# GasSensorCentral_v2_1.net
KiCad netlist of a schematic drawn in EAGLE
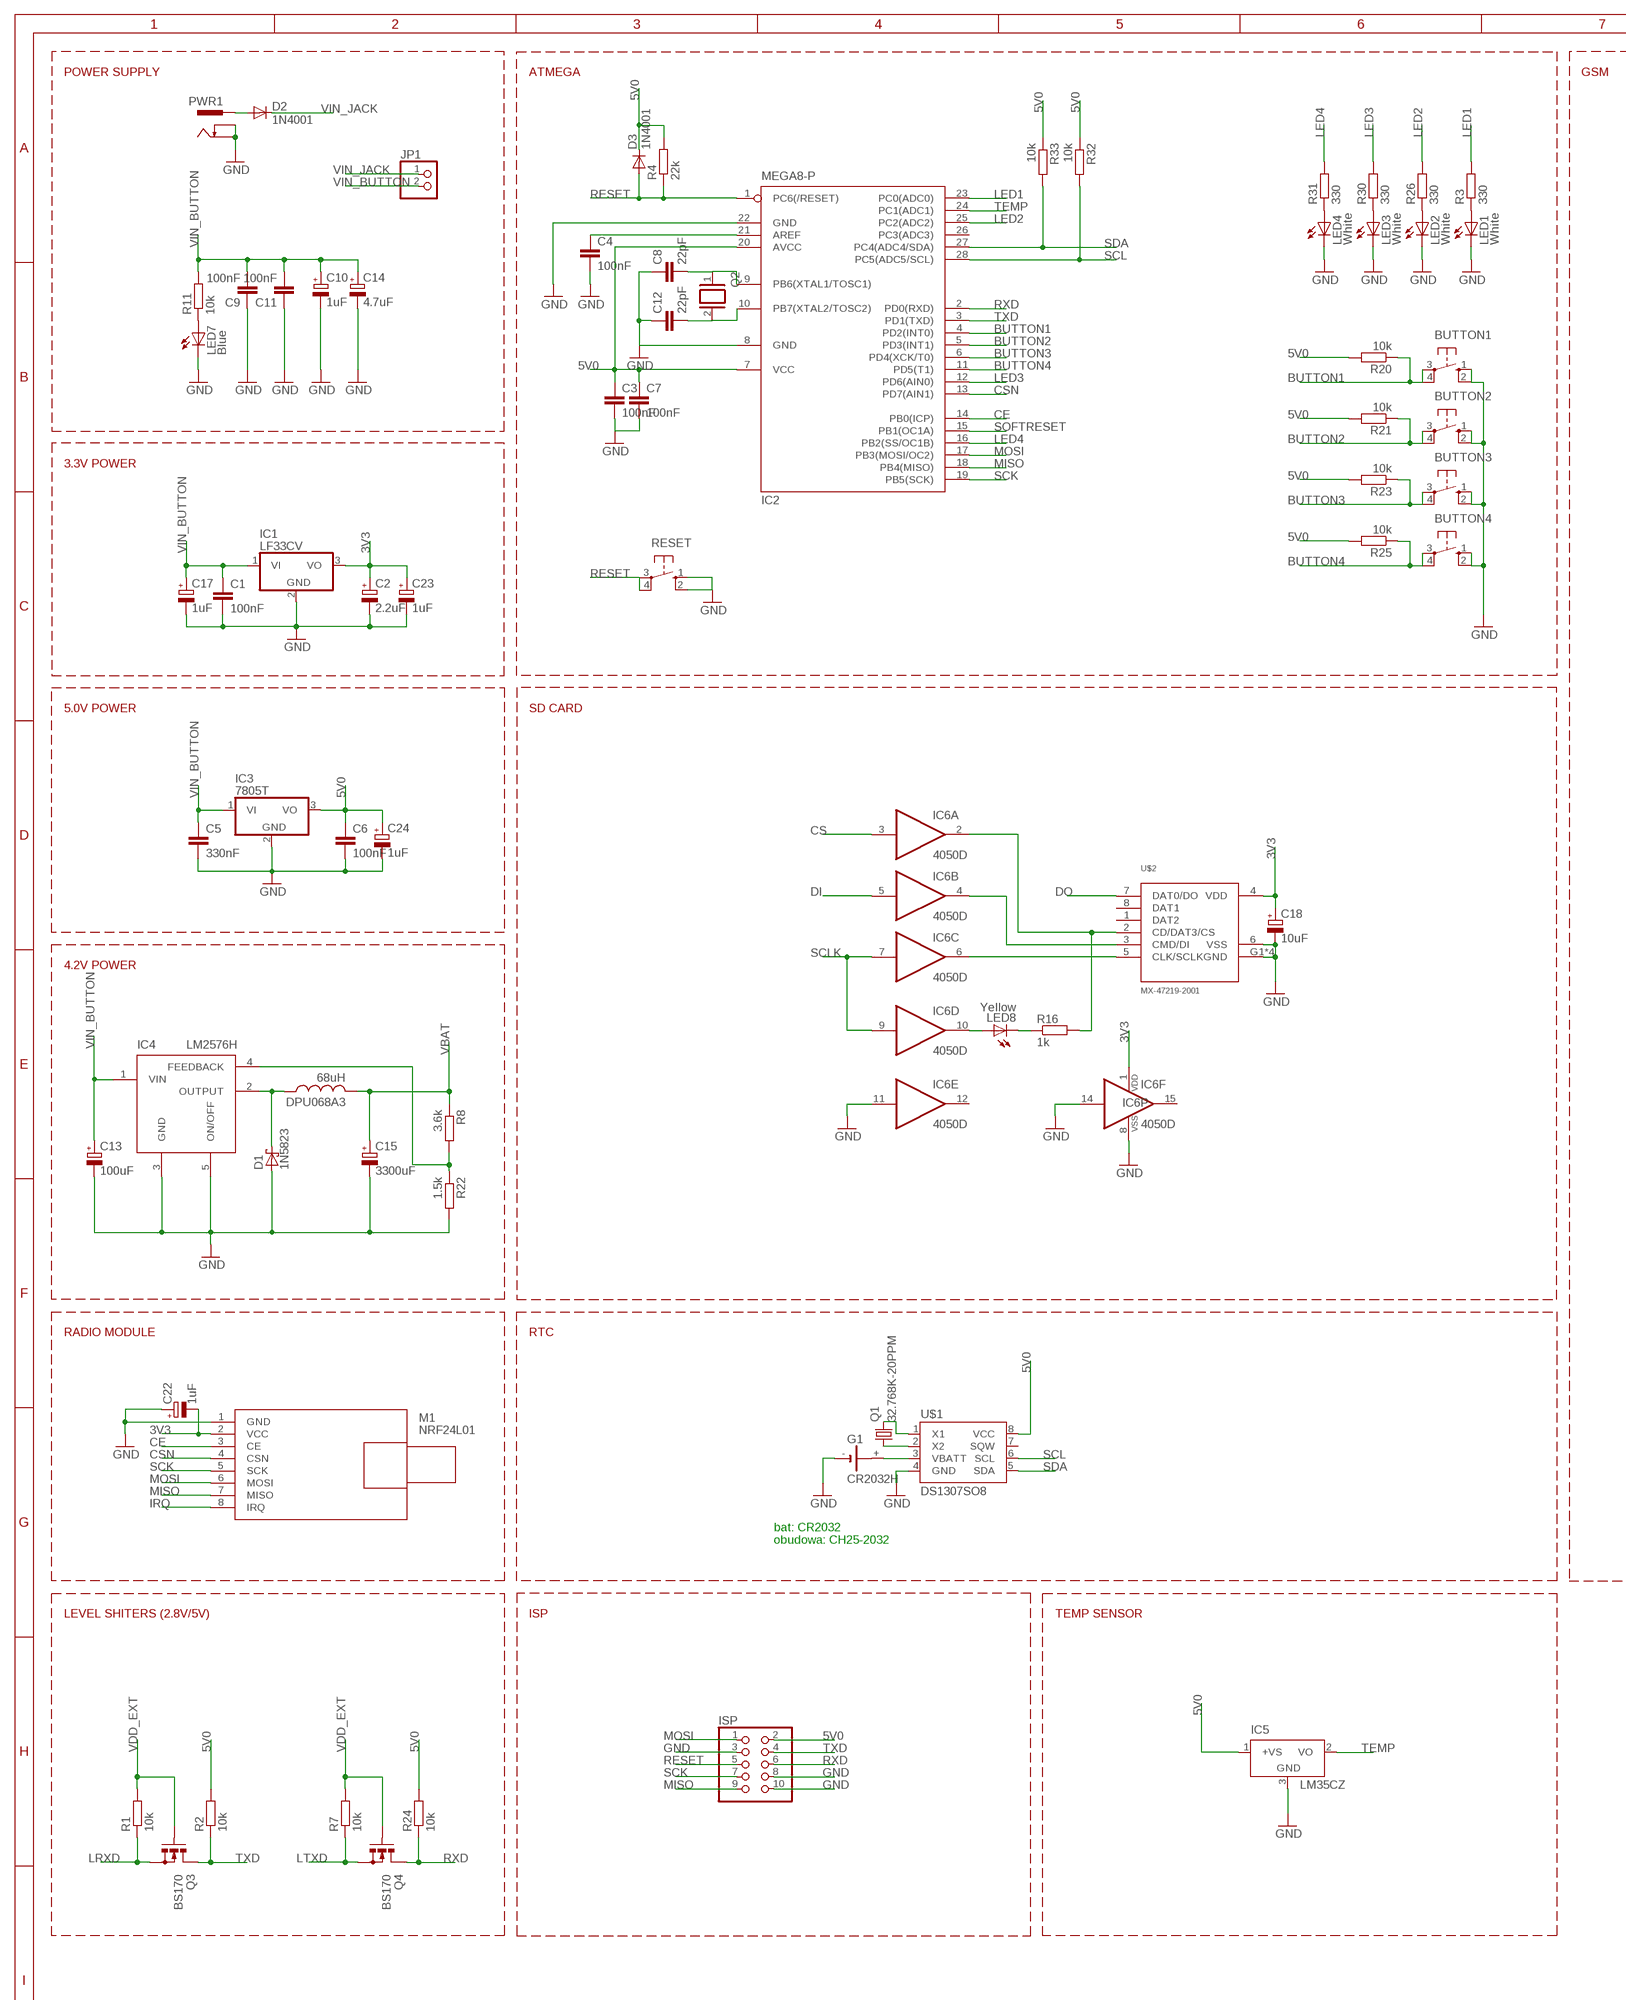
[diagram p0: schematic, sheet 1, part 1 of 2]
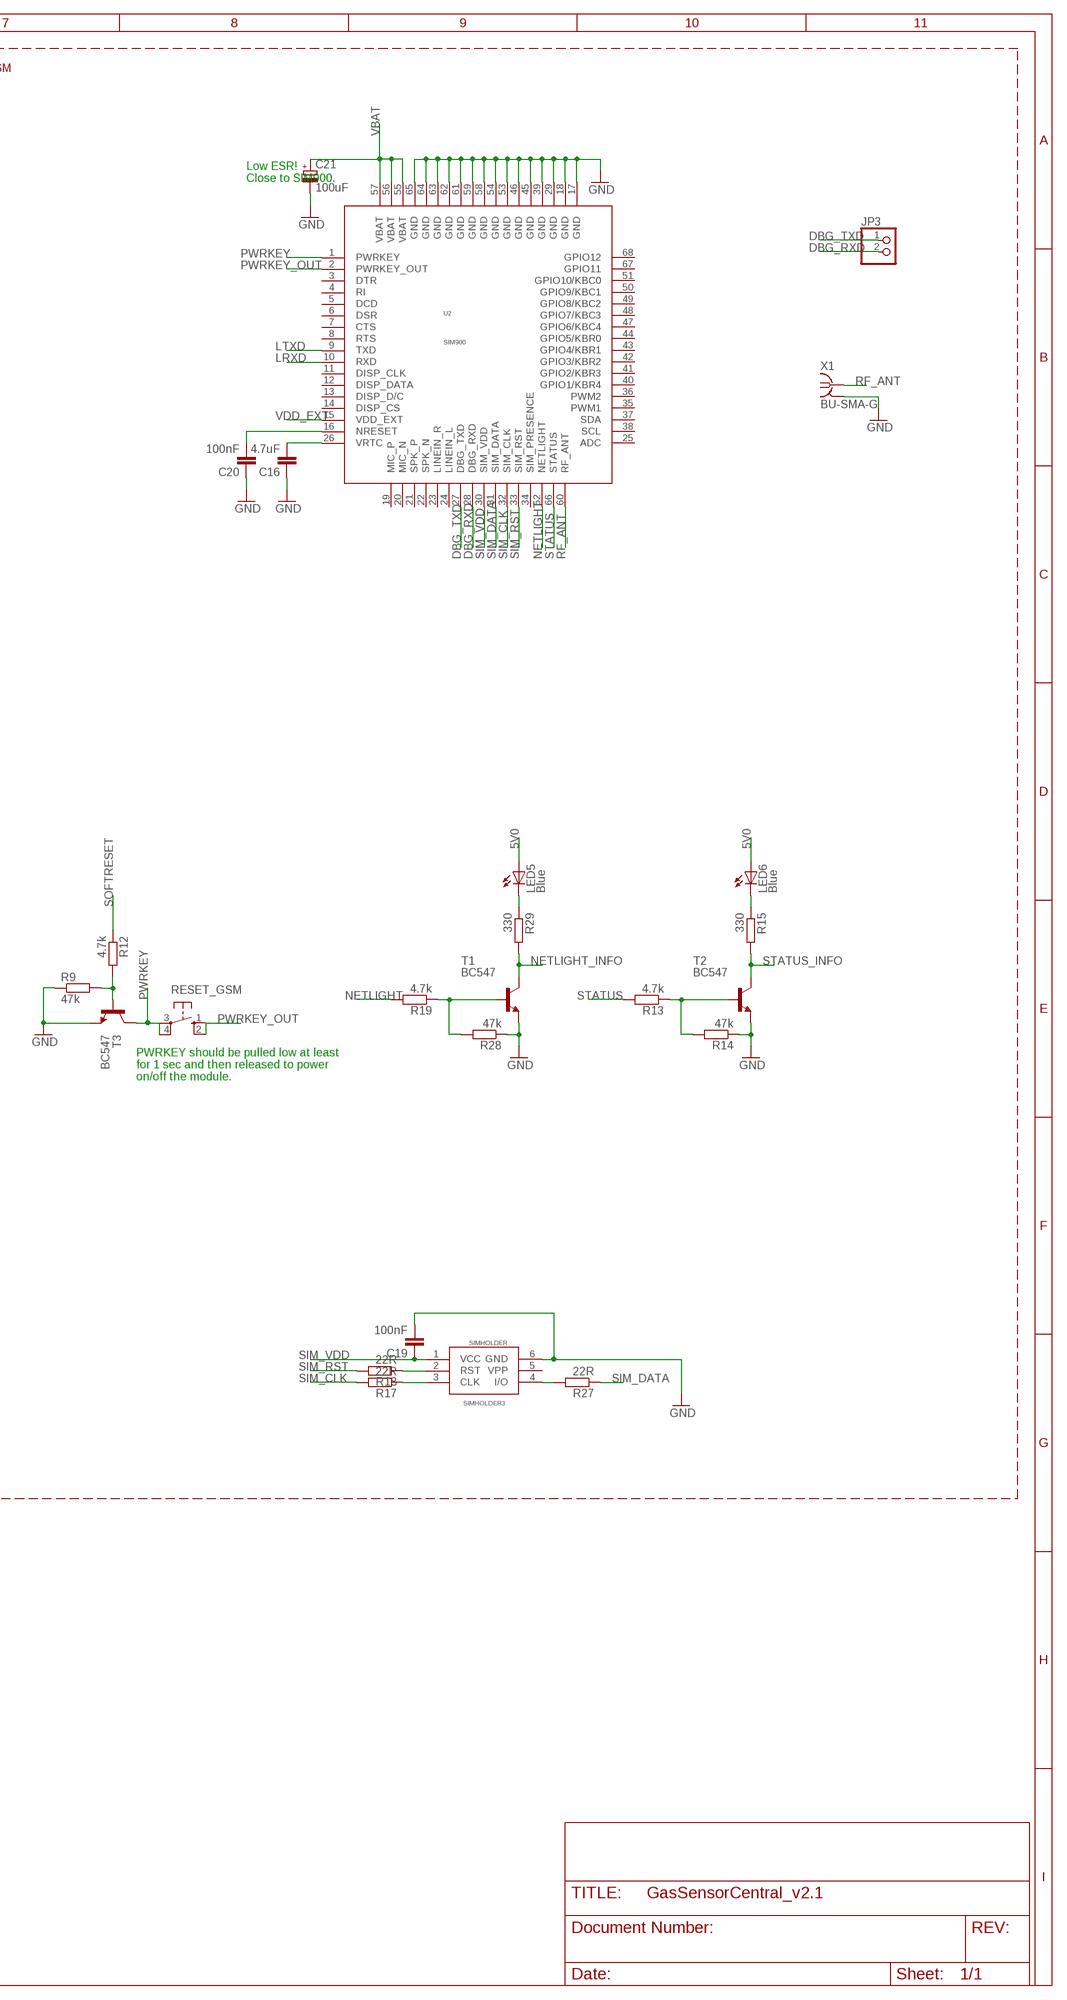
[diagram p1: schematic, sheet 1, part 2 of 2]

(export (version "E")
  (design (tool "Eeschema 10.0.6"))
  (components
    (comp (ref "BUTTON1")
      (value "10-XX")
      (footprint "eagle-import:B3F-10XX")
      (fields (field (name "MPN") "B3F-1000"))
      (libsource (lib "eagle-import") (part "10-XX"))
    )
    (comp (ref "BUTTON2")
      (value "10-XX")
      (footprint "eagle-import:B3F-10XX")
      (fields (field (name "MPN") "B3F-1000"))
      (libsource (lib "eagle-import") (part "10-XX"))
    )
    (comp (ref "BUTTON3")
      (value "10-XX")
      (footprint "eagle-import:B3F-10XX")
      (fields (field (name "MPN") "B3F-1000"))
      (libsource (lib "eagle-import") (part "10-XX"))
    )
    (comp (ref "BUTTON4")
      (value "10-XX")
      (footprint "eagle-import:B3F-10XX")
      (fields (field (name "MPN") "B3F-1000"))
      (libsource (lib "eagle-import") (part "10-XX"))
    )
    (comp (ref "C1")
      (value "100nF")
      (footprint "eagle-import:C025-025X050")
      (libsource (lib "eagle-import") (part "C-EU025-025X050"))
    )
    (comp (ref "C2")
      (value "2.2uF")
      (footprint "eagle-import:E2,5-5")
      (libsource (lib "eagle-import") (part "CPOL-EUE2.5-5"))
    )
    (comp (ref "C3")
      (value "100nF")
      (footprint "eagle-import:C025-025X050")
      (libsource (lib "eagle-import") (part "C-EU025-025X050"))
    )
    (comp (ref "C4")
      (value "100nF")
      (footprint "eagle-import:C025-025X050")
      (libsource (lib "eagle-import") (part "C-EU025-025X050"))
    )
    (comp (ref "C5")
      (value "330nF")
      (footprint "eagle-import:C025-025X050")
      (libsource (lib "eagle-import") (part "C-EU025-025X050"))
    )
    (comp (ref "C6")
      (value "100nF")
      (footprint "eagle-import:C025-025X050")
      (libsource (lib "eagle-import") (part "C-EU025-025X050"))
    )
    (comp (ref "C7")
      (value "100nF")
      (footprint "eagle-import:C025-025X050")
      (libsource (lib "eagle-import") (part "C-EU025-025X050"))
    )
    (comp (ref "C8")
      (value "22pF")
      (footprint "eagle-import:C025-025X050")
      (libsource (lib "eagle-import") (part "C-EU025-025X050"))
    )
    (comp (ref "C9")
      (value "100nF")
      (footprint "eagle-import:C025-025X050")
      (libsource (lib "eagle-import") (part "C-EU025-025X050"))
    )
    (comp (ref "C10")
      (value "1uF")
      (footprint "eagle-import:E2,5-5")
      (libsource (lib "eagle-import") (part "CPOL-EUE2.5-5"))
    )
    (comp (ref "C11")
      (value "100nF")
      (footprint "eagle-import:C025-025X050")
      (libsource (lib "eagle-import") (part "C-EU025-025X050"))
    )
    (comp (ref "C12")
      (value "22pF")
      (footprint "eagle-import:C025-025X050")
      (libsource (lib "eagle-import") (part "C-EU025-025X050"))
    )
    (comp (ref "C13")
      (value "100uF")
      (footprint "eagle-import:E2,5-5")
      (libsource (lib "eagle-import") (part "CPOL-EUE2.5-5"))
    )
    (comp (ref "C14")
      (value "4.7uF")
      (footprint "eagle-import:E2,5-5")
      (libsource (lib "eagle-import") (part "CPOL-EUE2.5-5"))
    )
    (comp (ref "C15")
      (value "3300uF")
      (footprint "eagle-import:E5-13")
      (libsource (lib "eagle-import") (part "CPOL-EUE5-13"))
    )
    (comp (ref "C16")
      (value "4.7uF")
      (footprint "eagle-import:C025-025X050")
      (libsource (lib "eagle-import") (part "C-EU025-025X050"))
    )
    (comp (ref "C17")
      (value "1uF")
      (footprint "eagle-import:E2,5-5")
      (libsource (lib "eagle-import") (part "CPOL-EUE2.5-5"))
    )
    (comp (ref "C18")
      (value "10uF")
      (footprint "eagle-import:E2,5-5")
      (libsource (lib "eagle-import") (part "CPOL-EUE2.5-5"))
    )
    (comp (ref "C19")
      (value "100nF")
      (footprint "eagle-import:C025-025X050")
      (libsource (lib "eagle-import") (part "C-EU025-025X050"))
    )
    (comp (ref "C20")
      (value "100nF")
      (footprint "eagle-import:C025-025X050")
      (libsource (lib "eagle-import") (part "C-EU025-025X050"))
    )
    (comp (ref "C21")
      (value "100uF")
      (footprint "eagle-import:E2,5-5")
      (libsource (lib "eagle-import") (part "CPOL-EUE2.5-5"))
    )
    (comp (ref "C22")
      (value "1uF")
      (footprint "eagle-import:E2,5-5")
      (libsource (lib "eagle-import") (part "CPOL-EUE2.5-5"))
    )
    (comp (ref "C23")
      (value "1uF")
      (footprint "eagle-import:E2,5-5")
      (libsource (lib "eagle-import") (part "CPOL-EUE2.5-5"))
    )
    (comp (ref "C24")
      (value "1uF")
      (footprint "eagle-import:E2,5-5")
      (libsource (lib "eagle-import") (part "CPOL-EUE2.5-5"))
    )
    (comp (ref "D1")
      (value "1N5823")
      (footprint "eagle-import:DO41-7.6")
      (libsource (lib "eagle-import") (part "1N5817-B"))
    )
    (comp (ref "D2")
      (value "1N4001")
      (footprint "eagle-import:DO41-10")
      (libsource (lib "eagle-import") (part "1N4004"))
    )
    (comp (ref "D3")
      (value "1N4001")
      (footprint "eagle-import:DO41-10")
      (libsource (lib "eagle-import") (part "1N4004"))
    )
    (comp (ref "DPU068A3")
      (value "68uH")
      (footprint "eagle-import:TJ4-U1")
      (libsource (lib "eagle-import") (part "L-USTJ4-U1"))
    )
    (comp (ref "G1")
      (value "CR2032H")
      (footprint "eagle-import:CR2032H")
      (libsource (lib "eagle-import") (part "CR2032H"))
    )
    (comp (ref "IC1")
      (value "LF33CV")
      (footprint "eagle-import:TO220H")
      (libsource (lib "eagle-import") (part "78T05"))
    )
    (comp (ref "IC2")
      (value "MEGA8-P")
      (footprint "eagle-import:DIL28-3")
      (libsource (lib "eagle-import") (part "MEGA8-P"))
    )
    (comp (ref "IC3")
      (value "7805T")
      (footprint "eagle-import:TO220H")
      (libsource (lib "eagle-import") (part "78T05"))
    )
    (comp (ref "IC4")
      (value "LM2576H")
      (footprint "eagle-import:TO220-52")
      (libsource (lib "eagle-import") (part "LM2576H"))
    )
    (comp (ref "IC5")
      (value "LM35CZ")
      (footprint "eagle-import:TO92")
      (libsource (lib "eagle-import") (part "LM35CZ"))
    )
    (comp (ref "IC6")
      (value "4050D")
      (footprint "eagle-import:SO16")
      (libsource (lib "eagle-import") (part "4050D"))
    )
    (comp (ref "ISP")
      (value "PINHD-2X5")
      (footprint "eagle-import:2X05")
      (libsource (lib "eagle-import") (part "PINHD-2X5"))
    )
    (comp (ref "JP1")
      (value "PINHD-1X2")
      (footprint "eagle-import:1X02")
      (libsource (lib "eagle-import") (part "PINHD-1X2"))
    )
    (comp (ref "JP3")
      (value "PINHD-1X2")
      (footprint "eagle-import:1X02")
      (libsource (lib "eagle-import") (part "PINHD-1X2"))
    )
    (comp (ref "LED1")
      (value "White")
      (footprint "eagle-import:LED3MM")
      (libsource (lib "eagle-import") (part "LED3MM"))
    )
    (comp (ref "LED2")
      (value "White")
      (footprint "eagle-import:LED3MM")
      (libsource (lib "eagle-import") (part "LED3MM"))
    )
    (comp (ref "LED3")
      (value "White")
      (footprint "eagle-import:LED3MM")
      (libsource (lib "eagle-import") (part "LED3MM"))
    )
    (comp (ref "LED4")
      (value "White")
      (footprint "eagle-import:LED3MM")
      (libsource (lib "eagle-import") (part "LED3MM"))
    )
    (comp (ref "LED5")
      (value "Blue")
      (footprint "eagle-import:LED3MM")
      (libsource (lib "eagle-import") (part "LED3MM"))
    )
    (comp (ref "LED6")
      (value "Blue")
      (footprint "eagle-import:LED3MM")
      (libsource (lib "eagle-import") (part "LED3MM"))
    )
    (comp (ref "LED7")
      (value "Blue")
      (footprint "eagle-import:LED3MM")
      (libsource (lib "eagle-import") (part "LED3MM"))
    )
    (comp (ref "LED8")
      (value "Yellow")
      (footprint "eagle-import:LED3MM")
      (libsource (lib "eagle-import") (part "LED3MM"))
    )
    (comp (ref "M1")
      (value "NRF24L01")
      (footprint "eagle-import:WIRELESS-NRD24L01-PA-EXT")
      (libsource (lib "eagle-import") (part "WIRELESS-NRF24L01-PA-EXT"))
    )
    (comp (ref "PWR1")
      (value "PWR-JAKPWR_JACK_UNI_MILLING")
      (footprint "eagle-import:PWR_JACK_UNI_MILLING")
      (libsource (lib "eagle-import") (part "PWR-JAKPWR_JACK_UNI_MILLING"))
    )
    (comp (ref "Q1")
      (value "32.768K-20PPM")
      (footprint "eagle-import:TC26V")
      (libsource (lib "eagle-import") (part "CRYSTALTC26V"))
    )
    (comp (ref "Q2")
      (value "XTAL/S")
      (footprint "eagle-import:QS")
      (libsource (lib "eagle-import") (part "XTAL/S"))
    )
    (comp (ref "Q3")
      (value "BS170")
      (footprint "eagle-import:SOT54E")
      (libsource (lib "eagle-import") (part "BS170"))
    )
    (comp (ref "Q4")
      (value "BS170")
      (footprint "eagle-import:SOT54E")
      (libsource (lib "eagle-import") (part "BS170"))
    )
    (comp (ref "R1")
      (value "10k")
      (footprint "eagle-import:0207_10")
      (libsource (lib "eagle-import") (part "R-EU_0207/10"))
    )
    (comp (ref "R2")
      (value "10k")
      (footprint "eagle-import:0207_10")
      (libsource (lib "eagle-import") (part "R-EU_0207/10"))
    )
    (comp (ref "R3")
      (value "330")
      (footprint "eagle-import:0207_10")
      (libsource (lib "eagle-import") (part "R-EU_0207/10"))
    )
    (comp (ref "R4")
      (value "22k")
      (footprint "eagle-import:0207_10")
      (libsource (lib "eagle-import") (part "R-EU_0207/10"))
    )
    (comp (ref "R7")
      (value "10k")
      (footprint "eagle-import:0207_10")
      (libsource (lib "eagle-import") (part "R-EU_0207/10"))
    )
    (comp (ref "R8")
      (value "3.6k")
      (footprint "eagle-import:0207_10")
      (libsource (lib "eagle-import") (part "R-EU_0207/10"))
    )
    (comp (ref "R9")
      (value "47k")
      (footprint "eagle-import:0207_10")
      (libsource (lib "eagle-import") (part "R-EU_0207/10"))
    )
    (comp (ref "R11")
      (value "10k")
      (footprint "eagle-import:0207_10")
      (libsource (lib "eagle-import") (part "R-EU_0207/10"))
    )
    (comp (ref "R12")
      (value "4.7k")
      (footprint "eagle-import:0207_10")
      (libsource (lib "eagle-import") (part "R-EU_0207/10"))
    )
    (comp (ref "R13")
      (value "4.7k")
      (footprint "eagle-import:0207_10")
      (libsource (lib "eagle-import") (part "R-EU_0207/10"))
    )
    (comp (ref "R14")
      (value "47k")
      (footprint "eagle-import:0207_10")
      (libsource (lib "eagle-import") (part "R-EU_0207/10"))
    )
    (comp (ref "R15")
      (value "330")
      (footprint "eagle-import:0207_10")
      (libsource (lib "eagle-import") (part "R-EU_0207/10"))
    )
    (comp (ref "R16")
      (value "1k")
      (footprint "eagle-import:0207_10")
      (libsource (lib "eagle-import") (part "R-EU_0207/10"))
    )
    (comp (ref "R17")
      (value "22R")
      (footprint "eagle-import:0207_10")
      (libsource (lib "eagle-import") (part "R-EU_0207/10"))
    )
    (comp (ref "R18")
      (value "22R")
      (footprint "eagle-import:0207_10")
      (libsource (lib "eagle-import") (part "R-EU_0207/10"))
    )
    (comp (ref "R19")
      (value "4.7k")
      (footprint "eagle-import:0207_10")
      (libsource (lib "eagle-import") (part "R-EU_0207/10"))
    )
    (comp (ref "R20")
      (value "10k")
      (footprint "eagle-import:0207_10")
      (libsource (lib "eagle-import") (part "R-EU_0207/10"))
    )
    (comp (ref "R21")
      (value "10k")
      (footprint "eagle-import:0207_10")
      (libsource (lib "eagle-import") (part "R-EU_0207/10"))
    )
    (comp (ref "R22")
      (value "1.5k")
      (footprint "eagle-import:0207_10")
      (libsource (lib "eagle-import") (part "R-EU_0207/10"))
    )
    (comp (ref "R23")
      (value "10k")
      (footprint "eagle-import:0207_10")
      (libsource (lib "eagle-import") (part "R-EU_0207/10"))
    )
    (comp (ref "R24")
      (value "10k")
      (footprint "eagle-import:0207_10")
      (libsource (lib "eagle-import") (part "R-EU_0207/10"))
    )
    (comp (ref "R25")
      (value "10k")
      (footprint "eagle-import:0207_10")
      (libsource (lib "eagle-import") (part "R-EU_0207/10"))
    )
    (comp (ref "R26")
      (value "330")
      (footprint "eagle-import:0207_10")
      (libsource (lib "eagle-import") (part "R-EU_0207/10"))
    )
    (comp (ref "R27")
      (value "22R")
      (footprint "eagle-import:0207_10")
      (libsource (lib "eagle-import") (part "R-EU_0207/10"))
    )
    (comp (ref "R28")
      (value "47k")
      (footprint "eagle-import:0207_10")
      (libsource (lib "eagle-import") (part "R-EU_0207/10"))
    )
    (comp (ref "R29")
      (value "330")
      (footprint "eagle-import:0207_10")
      (libsource (lib "eagle-import") (part "R-EU_0207/10"))
    )
    (comp (ref "R30")
      (value "330")
      (footprint "eagle-import:0207_10")
      (libsource (lib "eagle-import") (part "R-EU_0207/10"))
    )
    (comp (ref "R31")
      (value "330")
      (footprint "eagle-import:0207_10")
      (libsource (lib "eagle-import") (part "R-EU_0207/10"))
    )
    (comp (ref "R32")
      (value "10k")
      (footprint "eagle-import:0207_10")
      (libsource (lib "eagle-import") (part "R-EU_0207/10"))
    )
    (comp (ref "R33")
      (value "10k")
      (footprint "eagle-import:0207_10")
      (libsource (lib "eagle-import") (part "R-EU_0207/10"))
    )
    (comp (ref "RESET")
      (value "10-XX")
      (footprint "eagle-import:B3F-10XX")
      (fields (field (name "MPN") "B3F-1000"))
      (libsource (lib "eagle-import") (part "10-XX"))
    )
    (comp (ref "RESET_GSM")
      (value "10-XX")
      (footprint "eagle-import:B3F-10XX")
      (fields (field (name "MPN") "B3F-1000"))
      (libsource (lib "eagle-import") (part "10-XX"))
    )
    (comp (ref "SIMHOLDER")
      (value "SIMHOLDER3")
      (footprint "eagle-import:SIMHOLDER3")
      (libsource (lib "eagle-import") (part "SIMHOLDER3"))
    )
    (comp (ref "T1")
      (value "BC547")
      (footprint "eagle-import:TO92")
      (libsource (lib "eagle-import") (part "BC547"))
    )
    (comp (ref "T2")
      (value "BC547")
      (footprint "eagle-import:TO92")
      (libsource (lib "eagle-import") (part "BC547"))
    )
    (comp (ref "T3")
      (value "BC547")
      (footprint "eagle-import:TO92")
      (libsource (lib "eagle-import") (part "BC547"))
    )
    (comp (ref "U$1")
      (value "DS1307SO8")
      (footprint "eagle-import:SO08")
      (libsource (lib "eagle-import") (part "DS1307SO8"))
    )
    (comp (ref "U$2")
      (value "MX-47219-2001")
      (footprint "eagle-import:MX-47219-2001")
      (libsource (lib "eagle-import") (part "MX-47219-2001"))
    )
    (comp (ref "U2")
      (value "SIM900")
      (footprint "eagle-import:SIM900")
      (libsource (lib "eagle-import") (part "SIM900"))
    )
    (comp (ref "X1")
      (value "BU-SMA-G")
      (footprint "eagle-import:BU-SMA-G")
      (libsource (lib "eagle-import") (part "BU-SMA-G"))
    )
  )
  (nets
    (net (code "1") (name "/3V3") (class "Default")
      (node (ref "C18") (pin "+") (pinfunction "+_+") (pintype "passive"))
      (node (ref "C2") (pin "+") (pinfunction "+_+") (pintype "passive"))
      (node (ref "C22") (pin "-") (pinfunction "-_-") (pintype "passive"))
      (node (ref "C23") (pin "+") (pinfunction "+_+") (pintype "passive"))
      (node (ref "IC1") (pin "3") (pinfunction "VO_3") (pintype "passive"))
      (node (ref "IC6") (pin "1") (pinfunction "VDD_1") (pintype "power_in"))
      (node (ref "M1") (pin "2") (pinfunction "VCC_2") (pintype "power_in"))
      (node (ref "U$2") (pin "4") (pinfunction "VDD_4") (pintype "bidirectional"))
    )
    (net (code "2") (name "/5V0") (class "Default")
      (node (ref "C24") (pin "+") (pinfunction "+_+") (pintype "passive"))
      (node (ref "C3") (pin "1") (pinfunction "1_1") (pintype "passive"))
      (node (ref "C6") (pin "1") (pinfunction "1_1") (pintype "passive"))
      (node (ref "C7") (pin "1") (pinfunction "1_1") (pintype "passive"))
      (node (ref "D3") (pin "C") (pinfunction "C_C") (pintype "passive"))
      (node (ref "IC2") (pin "20") (pinfunction "AVCC_20") (pintype "power_in"))
      (node (ref "IC2") (pin "7") (pinfunction "VCC_7") (pintype "power_in"))
      (node (ref "IC3") (pin "3") (pinfunction "VO_3") (pintype "passive"))
      (node (ref "IC5") (pin "1") (pinfunction "+VS_1") (pintype "input"))
      (node (ref "ISP") (pin "2") (pinfunction "2_2") (pintype "passive"))
      (node (ref "LED5") (pin "A") (pinfunction "A_A") (pintype "passive"))
      (node (ref "LED6") (pin "A") (pinfunction "A_A") (pintype "passive"))
      (node (ref "R2") (pin "2") (pinfunction "2_2") (pintype "passive"))
      (node (ref "R20") (pin "2") (pinfunction "2_2") (pintype "passive"))
      (node (ref "R21") (pin "2") (pinfunction "2_2") (pintype "passive"))
      (node (ref "R23") (pin "2") (pinfunction "2_2") (pintype "passive"))
      (node (ref "R24") (pin "2") (pinfunction "2_2") (pintype "passive"))
      (node (ref "R25") (pin "2") (pinfunction "2_2") (pintype "passive"))
      (node (ref "R32") (pin "1") (pinfunction "1_1") (pintype "passive"))
      (node (ref "R33") (pin "1") (pinfunction "1_1") (pintype "passive"))
      (node (ref "R4") (pin "2") (pinfunction "2_2") (pintype "passive"))
      (node (ref "U$1") (pin "8") (pinfunction "VCC_8") (pintype "bidirectional"))
    )
    (net (code "3") (name "/BUTTON1") (class "Default")
      (node (ref "BUTTON1") (pin "3") (pinfunction "P_3") (pintype "passive"))
      (node (ref "BUTTON1") (pin "4") (pinfunction "P1_4") (pintype "passive"))
      (node (ref "IC2") (pin "4") (pinfunction "PD2(INT0)_4") (pintype "bidirectional"))
      (node (ref "R20") (pin "1") (pinfunction "1_1") (pintype "passive"))
    )
    (net (code "4") (name "/BUTTON2") (class "Default")
      (node (ref "BUTTON2") (pin "3") (pinfunction "P_3") (pintype "passive"))
      (node (ref "BUTTON2") (pin "4") (pinfunction "P1_4") (pintype "passive"))
      (node (ref "IC2") (pin "5") (pinfunction "PD3(INT1)_5") (pintype "bidirectional"))
      (node (ref "R21") (pin "1") (pinfunction "1_1") (pintype "passive"))
    )
    (net (code "5") (name "/BUTTON3") (class "Default")
      (node (ref "BUTTON3") (pin "3") (pinfunction "P_3") (pintype "passive"))
      (node (ref "BUTTON3") (pin "4") (pinfunction "P1_4") (pintype "passive"))
      (node (ref "IC2") (pin "6") (pinfunction "PD4(XCK/T0)_6") (pintype "bidirectional"))
      (node (ref "R23") (pin "1") (pinfunction "1_1") (pintype "passive"))
    )
    (net (code "6") (name "/BUTTON4") (class "Default")
      (node (ref "BUTTON4") (pin "3") (pinfunction "P_3") (pintype "passive"))
      (node (ref "BUTTON4") (pin "4") (pinfunction "P1_4") (pintype "passive"))
      (node (ref "IC2") (pin "11") (pinfunction "PD5(T1)_11") (pintype "bidirectional"))
      (node (ref "R25") (pin "1") (pinfunction "1_1") (pintype "passive"))
    )
    (net (code "7") (name "/CE") (class "Default")
      (node (ref "IC2") (pin "14") (pinfunction "PB0(ICP)_14") (pintype "bidirectional"))
      (node (ref "M1") (pin "3") (pinfunction "CE_3") (pintype "bidirectional"))
    )
    (net (code "8") (name "/CS") (class "Default")
      (node (ref "IC6") (pin "3") (pinfunction "I_3") (pintype "input"))
    )
    (net (code "9") (name "/CSN") (class "Default")
      (node (ref "IC2") (pin "13") (pinfunction "PD7(AIN1)_13") (pintype "bidirectional"))
      (node (ref "M1") (pin "4") (pinfunction "CSN_4") (pintype "bidirectional"))
    )
    (net (code "10") (name "/DBG_RXD") (class "Default")
      (node (ref "JP3") (pin "2") (pinfunction "2_2") (pintype "passive"))
      (node (ref "U2") (pin "28") (pinfunction "DBG_RXD_28") (pintype "input"))
    )
    (net (code "11") (name "/DBG_TXD") (class "Default")
      (node (ref "JP3") (pin "1") (pinfunction "1_1") (pintype "passive"))
      (node (ref "U2") (pin "27") (pinfunction "DBG_TXD_27") (pintype "output"))
    )
    (net (code "12") (name "/DI") (class "Default")
      (node (ref "IC6") (pin "5") (pinfunction "I_5") (pintype "input"))
    )
    (net (code "13") (name "/DO") (class "Default")
      (node (ref "U$2") (pin "7") (pinfunction "DAT0/DO_7") (pintype "bidirectional"))
    )
    (net (code "14") (name "/IRQ") (class "Default")
      (node (ref "M1") (pin "8") (pinfunction "IRQ_8") (pintype "bidirectional"))
    )
    (net (code "15") (name "/LED1") (class "Default")
      (node (ref "IC2") (pin "23") (pinfunction "PC0(ADC0)_23") (pintype "bidirectional"))
      (node (ref "R3") (pin "2") (pinfunction "2_2") (pintype "passive"))
    )
    (net (code "16") (name "/LED2") (class "Default")
      (node (ref "IC2") (pin "25") (pinfunction "PC2(ADC2)_25") (pintype "bidirectional"))
      (node (ref "R26") (pin "2") (pinfunction "2_2") (pintype "passive"))
    )
    (net (code "17") (name "/LED3") (class "Default")
      (node (ref "IC2") (pin "12") (pinfunction "PD6(AIN0)_12") (pintype "bidirectional"))
      (node (ref "R30") (pin "2") (pinfunction "2_2") (pintype "passive"))
    )
    (net (code "18") (name "/LED4") (class "Default")
      (node (ref "IC2") (pin "16") (pinfunction "PB2(SS/OC1B)_16") (pintype "bidirectional"))
      (node (ref "R31") (pin "2") (pinfunction "2_2") (pintype "passive"))
    )
    (net (code "19") (name "/LRXD") (class "Default")
      (node (ref "Q3") (pin "S") (pinfunction "S_S") (pintype "passive"))
      (node (ref "R1") (pin "1") (pinfunction "1_1") (pintype "passive"))
      (node (ref "U2") (pin "10") (pinfunction "RXD_10") (pintype "input"))
    )
    (net (code "20") (name "/LTXD") (class "Default")
      (node (ref "Q4") (pin "S") (pinfunction "S_S") (pintype "passive"))
      (node (ref "R7") (pin "1") (pinfunction "1_1") (pintype "passive"))
      (node (ref "U2") (pin "9") (pinfunction "TXD_9") (pintype "output"))
    )
    (net (code "21") (name "/MISO") (class "Default")
      (node (ref "IC2") (pin "18") (pinfunction "PB4(MISO)_18") (pintype "bidirectional"))
      (node (ref "ISP") (pin "9") (pinfunction "9_9") (pintype "passive"))
      (node (ref "M1") (pin "7") (pinfunction "MISO_7") (pintype "bidirectional"))
    )
    (net (code "22") (name "/MOSI") (class "Default")
      (node (ref "IC2") (pin "17") (pinfunction "PB3(MOSI/OC2)_17") (pintype "bidirectional"))
      (node (ref "ISP") (pin "1") (pinfunction "1_1") (pintype "passive"))
      (node (ref "M1") (pin "6") (pinfunction "MOSI_6") (pintype "bidirectional"))
    )
    (net (code "23") (name "/NETLIGHT") (class "Default")
      (node (ref "R19") (pin "2") (pinfunction "2_2") (pintype "passive"))
      (node (ref "U2") (pin "52") (pinfunction "NETLIGHT_52") (pintype "output"))
    )
    (net (code "24") (name "/NETLIGHT_INFO") (class "Default")
      (node (ref "R29") (pin "2") (pinfunction "2_2") (pintype "passive"))
      (node (ref "T1") (pin "3") (pinfunction "C_3") (pintype "passive"))
    )
    (net (code "25") (name "/PWRKEY") (class "Default")
      (node (ref "RESET_GSM") (pin "3") (pinfunction "P_3") (pintype "passive"))
      (node (ref "RESET_GSM") (pin "4") (pinfunction "P1_4") (pintype "passive"))
      (node (ref "T3") (pin "3") (pinfunction "C_3") (pintype "passive"))
      (node (ref "U2") (pin "1") (pinfunction "PWRKEY_1") (pintype "input"))
    )
    (net (code "26") (name "/PWRKEY_OUT") (class "Default")
      (node (ref "RESET_GSM") (pin "1") (pinfunction "S_1") (pintype "passive"))
      (node (ref "RESET_GSM") (pin "2") (pinfunction "S1_2") (pintype "passive"))
      (node (ref "U2") (pin "2") (pinfunction "PWRKEY_OUT_2") (pintype "output"))
    )
    (net (code "27") (name "/RESET") (class "Default")
      (node (ref "D3") (pin "A") (pinfunction "A_A") (pintype "passive"))
      (node (ref "IC2") (pin "1") (pinfunction "PC6(/RESET)_1") (pintype "bidirectional"))
      (node (ref "ISP") (pin "5") (pinfunction "5_5") (pintype "passive"))
      (node (ref "R4") (pin "1") (pinfunction "1_1") (pintype "passive"))
      (node (ref "RESET") (pin "3") (pinfunction "P_3") (pintype "passive"))
      (node (ref "RESET") (pin "4") (pinfunction "P1_4") (pintype "passive"))
    )
    (net (code "28") (name "/RF_ANT") (class "Default")
      (node (ref "U2") (pin "60") (pinfunction "RF_ANT_60") (pintype "bidirectional"))
      (node (ref "X1") (pin "1") (pinfunction "1_1") (pintype "passive"))
    )
    (net (code "29") (name "/RXD") (class "Default")
      (node (ref "IC2") (pin "2") (pinfunction "PD0(RXD)_2") (pintype "bidirectional"))
      (node (ref "ISP") (pin "6") (pinfunction "6_6") (pintype "passive"))
      (node (ref "Q4") (pin "D") (pinfunction "D_D") (pintype "passive"))
      (node (ref "R24") (pin "1") (pinfunction "1_1") (pintype "passive"))
    )
    (net (code "30") (name "/SCK") (class "Default")
      (node (ref "IC2") (pin "19") (pinfunction "PB5(SCK)_19") (pintype "bidirectional"))
      (node (ref "ISP") (pin "7") (pinfunction "7_7") (pintype "passive"))
      (node (ref "M1") (pin "5") (pinfunction "SCK_5") (pintype "bidirectional"))
    )
    (net (code "31") (name "/SCL") (class "Default")
      (node (ref "IC2") (pin "28") (pinfunction "PC5(ADC5/SCL)_28") (pintype "bidirectional"))
      (node (ref "R32") (pin "2") (pinfunction "2_2") (pintype "passive"))
      (node (ref "U$1") (pin "6") (pinfunction "SCL_6") (pintype "bidirectional"))
    )
    (net (code "32") (name "/SCLK") (class "Default")
      (node (ref "IC6") (pin "7") (pinfunction "I_7") (pintype "input"))
      (node (ref "IC6") (pin "9") (pinfunction "I_9") (pintype "input"))
    )
    (net (code "33") (name "/SDA") (class "Default")
      (node (ref "IC2") (pin "27") (pinfunction "PC4(ADC4/SDA)_27") (pintype "bidirectional"))
      (node (ref "R33") (pin "2") (pinfunction "2_2") (pintype "passive"))
      (node (ref "U$1") (pin "5") (pinfunction "SDA_5") (pintype "bidirectional"))
    )
    (net (code "34") (name "/SIM_CLK") (class "Default")
      (node (ref "R17") (pin "2") (pinfunction "2_2") (pintype "passive"))
      (node (ref "U2") (pin "32") (pinfunction "SIM_CLK_32") (pintype "output"))
    )
    (net (code "35") (name "/SIM_DATA") (class "Default")
      (node (ref "R27") (pin "1") (pinfunction "1_1") (pintype "passive"))
      (node (ref "U2") (pin "31") (pinfunction "SIM_DATA_31") (pintype "bidirectional"))
    )
    (net (code "36") (name "/SIM_RST") (class "Default")
      (node (ref "R18") (pin "2") (pinfunction "2_2") (pintype "passive"))
      (node (ref "U2") (pin "33") (pinfunction "SIM_RST_33") (pintype "output"))
    )
    (net (code "37") (name "/SIM_VDD") (class "Default")
      (node (ref "C19") (pin "1") (pinfunction "1_1") (pintype "passive"))
      (node (ref "SIMHOLDER") (pin "1") (pinfunction "VCC_1") (pintype "bidirectional"))
      (node (ref "U2") (pin "30") (pinfunction "SIM_VDD_30") (pintype "output"))
    )
    (net (code "38") (name "/SOFTRESET") (class "Default")
      (node (ref "IC2") (pin "15") (pinfunction "PB1(OC1A)_15") (pintype "bidirectional"))
      (node (ref "R12") (pin "1") (pinfunction "1_1") (pintype "passive"))
    )
    (net (code "39") (name "/STATUS") (class "Default")
      (node (ref "R13") (pin "2") (pinfunction "2_2") (pintype "passive"))
      (node (ref "U2") (pin "66") (pinfunction "STATUS_66") (pintype "output"))
    )
    (net (code "40") (name "/STATUS_INFO") (class "Default")
      (node (ref "R15") (pin "2") (pinfunction "2_2") (pintype "passive"))
      (node (ref "T2") (pin "3") (pinfunction "C_3") (pintype "passive"))
    )
    (net (code "41") (name "/TEMP") (class "Default")
      (node (ref "IC2") (pin "24") (pinfunction "PC1(ADC1)_24") (pintype "bidirectional"))
      (node (ref "IC5") (pin "2") (pinfunction "VO_2") (pintype "input"))
    )
    (net (code "42") (name "/TXD") (class "Default")
      (node (ref "IC2") (pin "3") (pinfunction "PD1(TXD)_3") (pintype "bidirectional"))
      (node (ref "ISP") (pin "4") (pinfunction "4_4") (pintype "passive"))
      (node (ref "Q3") (pin "D") (pinfunction "D_D") (pintype "passive"))
      (node (ref "R2") (pin "1") (pinfunction "1_1") (pintype "passive"))
    )
    (net (code "43") (name "/VBAT") (class "Default")
      (node (ref "C15") (pin "+") (pinfunction "+_+") (pintype "passive"))
      (node (ref "C21") (pin "+") (pinfunction "+_+") (pintype "passive"))
      (node (ref "DPU068A3") (pin "2") (pinfunction "2_2") (pintype "passive"))
      (node (ref "R8") (pin "1") (pinfunction "1_1") (pintype "passive"))
      (node (ref "U2") (pin "55") (pinfunction "VBAT_55") (pintype "power_in"))
      (node (ref "U2") (pin "56") (pinfunction "VBAT_56") (pintype "power_in"))
      (node (ref "U2") (pin "57") (pinfunction "VBAT_57") (pintype "power_in"))
    )
    (net (code "44") (name "/VDD_EXT") (class "Default")
      (node (ref "Q3") (pin "G") (pinfunction "G_G") (pintype "passive"))
      (node (ref "Q4") (pin "G") (pinfunction "G_G") (pintype "passive"))
      (node (ref "R1") (pin "2") (pinfunction "2_2") (pintype "passive"))
      (node (ref "R7") (pin "2") (pinfunction "2_2") (pintype "passive"))
      (node (ref "U2") (pin "15") (pinfunction "VDD_EXT_15") (pintype "output"))
    )
    (net (code "45") (name "/VIN_BUTTON") (class "Default")
      (node (ref "C1") (pin "1") (pinfunction "1_1") (pintype "passive"))
      (node (ref "C10") (pin "+") (pinfunction "+_+") (pintype "passive"))
      (node (ref "C11") (pin "2") (pinfunction "2_2") (pintype "passive"))
      (node (ref "C13") (pin "+") (pinfunction "+_+") (pintype "passive"))
      (node (ref "C14") (pin "+") (pinfunction "+_+") (pintype "passive"))
      (node (ref "C17") (pin "+") (pinfunction "+_+") (pintype "passive"))
      (node (ref "C5") (pin "1") (pinfunction "1_1") (pintype "passive"))
      (node (ref "C9") (pin "2") (pinfunction "2_2") (pintype "passive"))
      (node (ref "IC1") (pin "1") (pinfunction "VI_1") (pintype "input"))
      (node (ref "IC3") (pin "1") (pinfunction "VI_1") (pintype "input"))
      (node (ref "IC4") (pin "1") (pinfunction "VIN_1") (pintype "input"))
      (node (ref "JP1") (pin "2") (pinfunction "2_2") (pintype "passive"))
      (node (ref "R11") (pin "2") (pinfunction "2_2") (pintype "passive"))
    )
    (net (code "46") (name "/VIN_JACK") (class "Default")
      (node (ref "D2") (pin "C") (pinfunction "C_C") (pintype "passive"))
      (node (ref "JP1") (pin "1") (pinfunction "1_1") (pintype "passive"))
    )
    (net (code "47") (name "GND") (class "Default")
      (node (ref "BUTTON1") (pin "1") (pinfunction "S_1") (pintype "passive"))
      (node (ref "BUTTON1") (pin "2") (pinfunction "S1_2") (pintype "passive"))
      (node (ref "BUTTON2") (pin "1") (pinfunction "S_1") (pintype "passive"))
      (node (ref "BUTTON2") (pin "2") (pinfunction "S1_2") (pintype "passive"))
      (node (ref "BUTTON3") (pin "1") (pinfunction "S_1") (pintype "passive"))
      (node (ref "BUTTON3") (pin "2") (pinfunction "S1_2") (pintype "passive"))
      (node (ref "BUTTON4") (pin "1") (pinfunction "S_1") (pintype "passive"))
      (node (ref "BUTTON4") (pin "2") (pinfunction "S1_2") (pintype "passive"))
      (node (ref "C1") (pin "2") (pinfunction "2_2") (pintype "passive"))
      (node (ref "C10") (pin "-") (pinfunction "-_-") (pintype "passive"))
      (node (ref "C11") (pin "1") (pinfunction "1_1") (pintype "passive"))
      (node (ref "C12") (pin "1") (pinfunction "1_1") (pintype "passive"))
      (node (ref "C13") (pin "-") (pinfunction "-_-") (pintype "passive"))
      (node (ref "C14") (pin "-") (pinfunction "-_-") (pintype "passive"))
      (node (ref "C15") (pin "-") (pinfunction "-_-") (pintype "passive"))
      (node (ref "C16") (pin "1") (pinfunction "1_1") (pintype "passive"))
      (node (ref "C17") (pin "-") (pinfunction "-_-") (pintype "passive"))
      (node (ref "C18") (pin "-") (pinfunction "-_-") (pintype "passive"))
      (node (ref "C19") (pin "2") (pinfunction "2_2") (pintype "passive"))
      (node (ref "C2") (pin "-") (pinfunction "-_-") (pintype "passive"))
      (node (ref "C20") (pin "1") (pinfunction "1_1") (pintype "passive"))
      (node (ref "C21") (pin "-") (pinfunction "-_-") (pintype "passive"))
      (node (ref "C22") (pin "+") (pinfunction "+_+") (pintype "passive"))
      (node (ref "C23") (pin "-") (pinfunction "-_-") (pintype "passive"))
      (node (ref "C24") (pin "-") (pinfunction "-_-") (pintype "passive"))
      (node (ref "C3") (pin "2") (pinfunction "2_2") (pintype "passive"))
      (node (ref "C4") (pin "2") (pinfunction "2_2") (pintype "passive"))
      (node (ref "C5") (pin "2") (pinfunction "2_2") (pintype "passive"))
      (node (ref "C6") (pin "2") (pinfunction "2_2") (pintype "passive"))
      (node (ref "C7") (pin "2") (pinfunction "2_2") (pintype "passive"))
      (node (ref "C8") (pin "1") (pinfunction "1_1") (pintype "passive"))
      (node (ref "C9") (pin "1") (pinfunction "1_1") (pintype "passive"))
      (node (ref "D1") (pin "A") (pinfunction "A_A") (pintype "passive"))
      (node (ref "G1") (pin "-") (pinfunction "-_-") (pintype "passive"))
      (node (ref "IC1") (pin "2") (pinfunction "GND_2") (pintype "passive"))
      (node (ref "IC2") (pin "22") (pinfunction "GND_22") (pintype "power_in"))
      (node (ref "IC2") (pin "8") (pinfunction "GND_8") (pintype "power_in"))
      (node (ref "IC3") (pin "2") (pinfunction "GND_2") (pintype "passive"))
      (node (ref "IC4") (pin "3") (pinfunction "GND_3") (pintype "power_in"))
      (node (ref "IC4") (pin "5") (pinfunction "ON/OFF_5") (pintype "bidirectional"))
      (node (ref "IC5") (pin "3") (pinfunction "GND_3") (pintype "power_in"))
      (node (ref "IC6") (pin "11") (pinfunction "I_11") (pintype "input"))
      (node (ref "IC6") (pin "14") (pinfunction "I_14") (pintype "input"))
      (node (ref "IC6") (pin "8") (pinfunction "VSS_8") (pintype "power_in"))
      (node (ref "ISP") (pin "10") (pinfunction "10_10") (pintype "passive"))
      (node (ref "ISP") (pin "3") (pinfunction "3_3") (pintype "passive"))
      (node (ref "ISP") (pin "8") (pinfunction "8_8") (pintype "passive"))
      (node (ref "LED1") (pin "K") (pinfunction "C_K") (pintype "passive"))
      (node (ref "LED2") (pin "K") (pinfunction "C_K") (pintype "passive"))
      (node (ref "LED3") (pin "K") (pinfunction "C_K") (pintype "passive"))
      (node (ref "LED4") (pin "K") (pinfunction "C_K") (pintype "passive"))
      (node (ref "LED7") (pin "K") (pinfunction "C_K") (pintype "passive"))
      (node (ref "M1") (pin "1") (pinfunction "GND_1") (pintype "power_in"))
      (node (ref "PWR1") (pin "-") (pinfunction "-_-") (pintype "passive"))
      (node (ref "PWR1") (pin "--") (pinfunction "--_--") (pintype "passive"))
      (node (ref "R14") (pin "1") (pinfunction "1_1") (pintype "passive"))
      (node (ref "R22") (pin "2") (pinfunction "2_2") (pintype "passive"))
      (node (ref "R28") (pin "1") (pinfunction "1_1") (pintype "passive"))
      (node (ref "R9") (pin "1") (pinfunction "1_1") (pintype "passive"))
      (node (ref "RESET") (pin "1") (pinfunction "S_1") (pintype "passive"))
      (node (ref "RESET") (pin "2") (pinfunction "S1_2") (pintype "passive"))
      (node (ref "SIMHOLDER") (pin "6") (pinfunction "GND_6") (pintype "bidirectional"))
      (node (ref "T1") (pin "1") (pinfunction "E_1") (pintype "passive"))
      (node (ref "T2") (pin "1") (pinfunction "E_1") (pintype "passive"))
      (node (ref "T3") (pin "1") (pinfunction "E_1") (pintype "passive"))
      (node (ref "U$1") (pin "4") (pinfunction "GND_4") (pintype "bidirectional"))
      (node (ref "U$2") (pin "6") (pinfunction "VSS_6") (pintype "bidirectional"))
      (node (ref "U$2") (pin "G1") (pinfunction "GND_G1") (pintype "bidirectional"))
      (node (ref "U$2") (pin "G2") (pinfunction "GND_G2") (pintype "bidirectional"))
      (node (ref "U$2") (pin "G3") (pinfunction "GND_G3") (pintype "bidirectional"))
      (node (ref "U$2") (pin "G4") (pinfunction "GND_G4") (pintype "bidirectional"))
      (node (ref "U2") (pin "17") (pinfunction "GND_17") (pintype "power_in"))
      (node (ref "U2") (pin "18") (pinfunction "GND_18") (pintype "power_in"))
      (node (ref "U2") (pin "29") (pinfunction "GND_29") (pintype "power_in"))
      (node (ref "U2") (pin "39") (pinfunction "GND_39") (pintype "power_in"))
      (node (ref "U2") (pin "45") (pinfunction "GND_45") (pintype "power_in"))
      (node (ref "U2") (pin "46") (pinfunction "GND_46") (pintype "power_in"))
      (node (ref "U2") (pin "53") (pinfunction "GND_53") (pintype "power_in"))
      (node (ref "U2") (pin "54") (pinfunction "GND_54") (pintype "power_in"))
      (node (ref "U2") (pin "58") (pinfunction "GND_58") (pintype "power_in"))
      (node (ref "U2") (pin "59") (pinfunction "GND_59") (pintype "power_in"))
      (node (ref "U2") (pin "61") (pinfunction "GND_61") (pintype "power_in"))
      (node (ref "U2") (pin "62") (pinfunction "GND_62") (pintype "power_in"))
      (node (ref "U2") (pin "63") (pinfunction "GND_63") (pintype "power_in"))
      (node (ref "U2") (pin "64") (pinfunction "GND_64") (pintype "power_in"))
      (node (ref "U2") (pin "65") (pinfunction "GND_65") (pintype "power_in"))
      (node (ref "X1") (pin "2") (pinfunction "2_2") (pintype "passive"))
      (node (ref "X1") (pin "3") (pinfunction "2_3") (pintype "passive"))
      (node (ref "X1") (pin "4") (pinfunction "2_4") (pintype "passive"))
      (node (ref "X1") (pin "5") (pinfunction "2_5") (pintype "passive"))
    )
    (net (code "48") (name "Net-(D2-PadA)") (class "Default")
      (node (ref "D2") (pin "A") (pinfunction "A_A") (pintype "passive"))
      (node (ref "PWR1") (pin "+") (pinfunction "+_+") (pintype "passive"))
    )
    (net (code "49") (name "Net-(IC2-AREF)") (class "Default")
      (node (ref "C4") (pin "1") (pinfunction "1_1") (pintype "passive"))
      (node (ref "IC2") (pin "21") (pinfunction "AREF_21") (pintype "passive"))
    )
    (net (code "50") (name "Net-(IC2-PB6(XTAL1{slash}TOSC1))") (class "Default")
      (node (ref "C8") (pin "2") (pinfunction "2_2") (pintype "passive"))
      (node (ref "IC2") (pin "9") (pinfunction "PB6(XTAL1/TOSC1)_9") (pintype "bidirectional"))
      (node (ref "Q2") (pin "1") (pinfunction "1_1") (pintype "passive"))
    )
    (net (code "51") (name "Net-(IC2-PB7(XTAL2{slash}TOSC2))") (class "Default")
      (node (ref "C12") (pin "2") (pinfunction "2_2") (pintype "passive"))
      (node (ref "IC2") (pin "10") (pinfunction "PB7(XTAL2/TOSC2)_10") (pintype "bidirectional"))
      (node (ref "Q2") (pin "2") (pinfunction "2_2") (pintype "passive"))
    )
    (net (code "52") (name "Net-(IC4-FEEDBACK)") (class "Default")
      (node (ref "IC4") (pin "4") (pinfunction "FEEDBACK_4") (pintype "bidirectional"))
      (node (ref "R22") (pin "1") (pinfunction "1_1") (pintype "passive"))
      (node (ref "R8") (pin "2") (pinfunction "2_2") (pintype "passive"))
    )
    (net (code "53") (name "Net-(IC4-OUTPUT)") (class "Default")
      (node (ref "D1") (pin "C") (pinfunction "C_C") (pintype "passive"))
      (node (ref "DPU068A3") (pin "1") (pinfunction "1_1") (pintype "passive"))
      (node (ref "IC4") (pin "2") (pinfunction "OUTPUT_2") (pintype "output"))
    )
    (net (code "54") (name "Net-(IC6A-O)") (class "Default")
      (node (ref "IC6") (pin "2") (pinfunction "O_2") (pintype "output"))
      (node (ref "R16") (pin "2") (pinfunction "2_2") (pintype "passive"))
      (node (ref "U$2") (pin "2") (pinfunction "CD/DAT3/CS_2") (pintype "bidirectional"))
    )
    (net (code "55") (name "Net-(IC6B-O)") (class "Default")
      (node (ref "IC6") (pin "4") (pinfunction "O_4") (pintype "output"))
      (node (ref "U$2") (pin "3") (pinfunction "CMD/DI_3") (pintype "bidirectional"))
    )
    (net (code "56") (name "Net-(IC6C-O)") (class "Default")
      (node (ref "IC6") (pin "6") (pinfunction "O_6") (pintype "output"))
      (node (ref "U$2") (pin "5") (pinfunction "CLK/SCLK_5") (pintype "bidirectional"))
    )
    (net (code "57") (name "Net-(IC6D-O)") (class "Default")
      (node (ref "IC6") (pin "10") (pinfunction "O_10") (pintype "output"))
      (node (ref "LED8") (pin "A") (pinfunction "A_A") (pintype "passive"))
    )
    (net (code "58") (name "Net-(LED1-PadA)") (class "Default")
      (node (ref "LED1") (pin "A") (pinfunction "A_A") (pintype "passive"))
      (node (ref "R3") (pin "1") (pinfunction "1_1") (pintype "passive"))
    )
    (net (code "59") (name "Net-(LED2-PadA)") (class "Default")
      (node (ref "LED2") (pin "A") (pinfunction "A_A") (pintype "passive"))
      (node (ref "R26") (pin "1") (pinfunction "1_1") (pintype "passive"))
    )
    (net (code "60") (name "Net-(LED3-PadA)") (class "Default")
      (node (ref "LED3") (pin "A") (pinfunction "A_A") (pintype "passive"))
      (node (ref "R30") (pin "1") (pinfunction "1_1") (pintype "passive"))
    )
    (net (code "61") (name "Net-(LED4-PadA)") (class "Default")
      (node (ref "LED4") (pin "A") (pinfunction "A_A") (pintype "passive"))
      (node (ref "R31") (pin "1") (pinfunction "1_1") (pintype "passive"))
    )
    (net (code "62") (name "Net-(LED5-C)") (class "Default")
      (node (ref "LED5") (pin "K") (pinfunction "C_K") (pintype "passive"))
      (node (ref "R29") (pin "1") (pinfunction "1_1") (pintype "passive"))
    )
    (net (code "63") (name "Net-(LED6-C)") (class "Default")
      (node (ref "LED6") (pin "K") (pinfunction "C_K") (pintype "passive"))
      (node (ref "R15") (pin "1") (pinfunction "1_1") (pintype "passive"))
    )
    (net (code "64") (name "Net-(LED7-PadA)") (class "Default")
      (node (ref "LED7") (pin "A") (pinfunction "A_A") (pintype "passive"))
      (node (ref "R11") (pin "1") (pinfunction "1_1") (pintype "passive"))
    )
    (net (code "65") (name "Net-(LED8-C)") (class "Default")
      (node (ref "LED8") (pin "K") (pinfunction "C_K") (pintype "passive"))
      (node (ref "R16") (pin "1") (pinfunction "1_1") (pintype "passive"))
    )
    (net (code "66") (name "Net-(SIMHOLDER-CLK)") (class "Default")
      (node (ref "R17") (pin "1") (pinfunction "1_1") (pintype "passive"))
      (node (ref "SIMHOLDER") (pin "3") (pinfunction "CLK_3") (pintype "bidirectional"))
    )
    (net (code "67") (name "Net-(SIMHOLDER-I{slash}O)") (class "Default")
      (node (ref "R27") (pin "2") (pinfunction "2_2") (pintype "passive"))
      (node (ref "SIMHOLDER") (pin "4") (pinfunction "I/O_4") (pintype "bidirectional"))
    )
    (net (code "68") (name "Net-(SIMHOLDER-RST)") (class "Default")
      (node (ref "R18") (pin "1") (pinfunction "1_1") (pintype "passive"))
      (node (ref "SIMHOLDER") (pin "2") (pinfunction "RST_2") (pintype "bidirectional"))
    )
    (net (code "69") (name "Net-(T1-B)") (class "Default")
      (node (ref "R19") (pin "1") (pinfunction "1_1") (pintype "passive"))
      (node (ref "R28") (pin "2") (pinfunction "2_2") (pintype "passive"))
      (node (ref "T1") (pin "2") (pinfunction "B_2") (pintype "passive"))
    )
    (net (code "70") (name "Net-(T2-B)") (class "Default")
      (node (ref "R13") (pin "1") (pinfunction "1_1") (pintype "passive"))
      (node (ref "R14") (pin "2") (pinfunction "2_2") (pintype "passive"))
      (node (ref "T2") (pin "2") (pinfunction "B_2") (pintype "passive"))
    )
    (net (code "71") (name "Net-(T3-B)") (class "Default")
      (node (ref "R12") (pin "2") (pinfunction "2_2") (pintype "passive"))
      (node (ref "R9") (pin "2") (pinfunction "2_2") (pintype "passive"))
      (node (ref "T3") (pin "2") (pinfunction "B_2") (pintype "passive"))
    )
    (net (code "72") (name "Net-(U$1-VBATT)") (class "Default")
      (node (ref "G1") (pin "+") (pinfunction "+_+") (pintype "passive"))
      (node (ref "U$1") (pin "3") (pinfunction "VBATT_3") (pintype "bidirectional"))
    )
    (net (code "73") (name "Net-(U$1-X1)") (class "Default")
      (node (ref "Q1") (pin "2") (pinfunction "2_2") (pintype "passive"))
      (node (ref "U$1") (pin "1") (pinfunction "X1_1") (pintype "bidirectional"))
    )
    (net (code "74") (name "Net-(U$1-X2)") (class "Default")
      (node (ref "Q1") (pin "1") (pinfunction "1_1") (pintype "passive"))
      (node (ref "U$1") (pin "2") (pinfunction "X2_2") (pintype "bidirectional"))
    )
    (net (code "75") (name "Net-(U2-NRESET)") (class "Default")
      (node (ref "C20") (pin "2") (pinfunction "2_2") (pintype "passive"))
      (node (ref "U2") (pin "16") (pinfunction "NRESET_16") (pintype "input"))
    )
    (net (code "76") (name "Net-(U2-VRTC)") (class "Default")
      (node (ref "C16") (pin "2") (pinfunction "2_2") (pintype "passive"))
      (node (ref "U2") (pin "26") (pinfunction "VRTC_26") (pintype "bidirectional"))
    )
    (net (code "77") (name "unconnected-(IC2-PC3(ADC3)-Pad26)") (class "Default")
      (node (ref "IC2") (pin "26") (pinfunction "PC3(ADC3)_26") (pintype "bidirectional"))
    )
    (net (code "78") (name "unconnected-(IC6E-O-Pad12)") (class "Default")
      (node (ref "IC6") (pin "12") (pinfunction "O_12") (pintype "output"))
    )
    (net (code "79") (name "unconnected-(IC6F-O-Pad15)") (class "Default")
      (node (ref "IC6") (pin "15") (pinfunction "O_15") (pintype "output"))
    )
    (net (code "80") (name "unconnected-(SIMHOLDER-VPP-Pad5)") (class "Default")
      (node (ref "SIMHOLDER") (pin "5") (pinfunction "VPP_5") (pintype "bidirectional"))
    )
    (net (code "81") (name "unconnected-(U$1-SQW-Pad7)") (class "Default")
      (node (ref "U$1") (pin "7") (pinfunction "SQW_7") (pintype "bidirectional"))
    )
    (net (code "82") (name "unconnected-(U$2-DAT1-Pad8)") (class "Default")
      (node (ref "U$2") (pin "8") (pinfunction "DAT1_8") (pintype "bidirectional"))
    )
    (net (code "83") (name "unconnected-(U$2-DAT2-Pad1)") (class "Default")
      (node (ref "U$2") (pin "1") (pinfunction "DAT2_1") (pintype "bidirectional"))
    )
    (net (code "84") (name "unconnected-(U2-ADC-Pad25)") (class "Default")
      (node (ref "U2") (pin "25") (pinfunction "ADC_25") (pintype "input"))
    )
    (net (code "85") (name "unconnected-(U2-CTS-Pad7)") (class "Default")
      (node (ref "U2") (pin "7") (pinfunction "CTS_7") (pintype "output"))
    )
    (net (code "86") (name "unconnected-(U2-DCD-Pad5)") (class "Default")
      (node (ref "U2") (pin "5") (pinfunction "DCD_5") (pintype "output"))
    )
    (net (code "87") (name "unconnected-(U2-DISP_CLK-Pad11)") (class "Default")
      (node (ref "U2") (pin "11") (pinfunction "DISP_CLK_11") (pintype "output"))
    )
    (net (code "88") (name "unconnected-(U2-DISP_CS-Pad14)") (class "Default")
      (node (ref "U2") (pin "14") (pinfunction "DISP_CS_14") (pintype "output"))
    )
    (net (code "89") (name "unconnected-(U2-DISP_DATA-Pad12)") (class "Default")
      (node (ref "U2") (pin "12") (pinfunction "DISP_DATA_12") (pintype "bidirectional"))
    )
    (net (code "90") (name "unconnected-(U2-DISP_D{slash}C-Pad13)") (class "Default")
      (node (ref "U2") (pin "13") (pinfunction "DISP_D/C_13") (pintype "output"))
    )
    (net (code "91") (name "unconnected-(U2-DSR-Pad6)") (class "Default")
      (node (ref "U2") (pin "6") (pinfunction "DSR_6") (pintype "output"))
    )
    (net (code "92") (name "unconnected-(U2-DTR-Pad3)") (class "Default")
      (node (ref "U2") (pin "3") (pinfunction "DTR_3") (pintype "input"))
    )
    (net (code "93") (name "unconnected-(U2-GPIO1{slash}KBR4-Pad40)") (class "Default")
      (node (ref "U2") (pin "40") (pinfunction "GPIO1/KBR4_40") (pintype "output"))
    )
    (net (code "94") (name "unconnected-(U2-GPIO2{slash}KBR3-Pad41)") (class "Default")
      (node (ref "U2") (pin "41") (pinfunction "GPIO2/KBR3_41") (pintype "output"))
    )
    (net (code "95") (name "unconnected-(U2-GPIO3{slash}KBR2-Pad42)") (class "Default")
      (node (ref "U2") (pin "42") (pinfunction "GPIO3/KBR2_42") (pintype "output"))
    )
    (net (code "96") (name "unconnected-(U2-GPIO4{slash}KBR1-Pad43)") (class "Default")
      (node (ref "U2") (pin "43") (pinfunction "GPIO4/KBR1_43") (pintype "output"))
    )
    (net (code "97") (name "unconnected-(U2-GPIO5{slash}KBR0-Pad44)") (class "Default")
      (node (ref "U2") (pin "44") (pinfunction "GPIO5/KBR0_44") (pintype "output"))
    )
    (net (code "98") (name "unconnected-(U2-GPIO6{slash}KBC4-Pad47)") (class "Default")
      (node (ref "U2") (pin "47") (pinfunction "GPIO6/KBC4_47") (pintype "input"))
    )
    (net (code "99") (name "unconnected-(U2-GPIO7{slash}KBC3-Pad48)") (class "Default")
      (node (ref "U2") (pin "48") (pinfunction "GPIO7/KBC3_48") (pintype "bidirectional"))
    )
    (net (code "100") (name "unconnected-(U2-GPIO8{slash}KBC2-Pad49)") (class "Default")
      (node (ref "U2") (pin "49") (pinfunction "GPIO8/KBC2_49") (pintype "input"))
    )
    (net (code "101") (name "unconnected-(U2-GPIO9{slash}KBC1-Pad50)") (class "Default")
      (node (ref "U2") (pin "50") (pinfunction "GPIO9/KBC1_50") (pintype "input"))
    )
    (net (code "102") (name "unconnected-(U2-GPIO10{slash}KBC0-Pad51)") (class "Default")
      (node (ref "U2") (pin "51") (pinfunction "GPIO10/KBC0_51") (pintype "bidirectional"))
    )
    (net (code "103") (name "unconnected-(U2-GPIO11-Pad67)") (class "Default")
      (node (ref "U2") (pin "67") (pinfunction "GPIO11_67") (pintype "bidirectional"))
    )
    (net (code "104") (name "unconnected-(U2-GPIO12-Pad68)") (class "Default")
      (node (ref "U2") (pin "68") (pinfunction "GPIO12_68") (pintype "bidirectional"))
    )
    (net (code "105") (name "unconnected-(U2-LINEIN_L-Pad24)") (class "Default")
      (node (ref "U2") (pin "24") (pinfunction "LINEIN_L_24") (pintype "input"))
    )
    (net (code "106") (name "unconnected-(U2-LINEIN_R-Pad23)") (class "Default")
      (node (ref "U2") (pin "23") (pinfunction "LINEIN_R_23") (pintype "input"))
    )
    (net (code "107") (name "unconnected-(U2-MIC_N-Pad20)") (class "Default")
      (node (ref "U2") (pin "20") (pinfunction "MIC_N_20") (pintype "input"))
    )
    (net (code "108") (name "unconnected-(U2-MIC_P-Pad19)") (class "Default")
      (node (ref "U2") (pin "19") (pinfunction "MIC_P_19") (pintype "input"))
    )
    (net (code "109") (name "unconnected-(U2-PWM1-Pad35)") (class "Default")
      (node (ref "U2") (pin "35") (pinfunction "PWM1_35") (pintype "output"))
    )
    (net (code "110") (name "unconnected-(U2-PWM2-Pad36)") (class "Default")
      (node (ref "U2") (pin "36") (pinfunction "PWM2_36") (pintype "output"))
    )
    (net (code "111") (name "unconnected-(U2-RI-Pad4)") (class "Default")
      (node (ref "U2") (pin "4") (pinfunction "RI_4") (pintype "output"))
    )
    (net (code "112") (name "unconnected-(U2-RTS-Pad8)") (class "Default")
      (node (ref "U2") (pin "8") (pinfunction "RTS_8") (pintype "input"))
    )
    (net (code "113") (name "unconnected-(U2-SCL-Pad38)") (class "Default")
      (node (ref "U2") (pin "38") (pinfunction "SCL_38") (pintype "output"))
    )
    (net (code "114") (name "unconnected-(U2-SDA-Pad37)") (class "Default")
      (node (ref "U2") (pin "37") (pinfunction "SDA_37") (pintype "bidirectional"))
    )
    (net (code "115") (name "unconnected-(U2-SIM_PRESENCE-Pad34)") (class "Default")
      (node (ref "U2") (pin "34") (pinfunction "SIM_PRESENCE_34") (pintype "input"))
    )
    (net (code "116") (name "unconnected-(U2-SPK_N-Pad22)") (class "Default")
      (node (ref "U2") (pin "22") (pinfunction "SPK_N_22") (pintype "output"))
    )
    (net (code "117") (name "unconnected-(U2-SPK_P-Pad21)") (class "Default")
      (node (ref "U2") (pin "21") (pinfunction "SPK_P_21") (pintype "output"))
    )
  )
)
